# Top_Level.net
KiCad netlist of a schematic drawn in Altium Designer
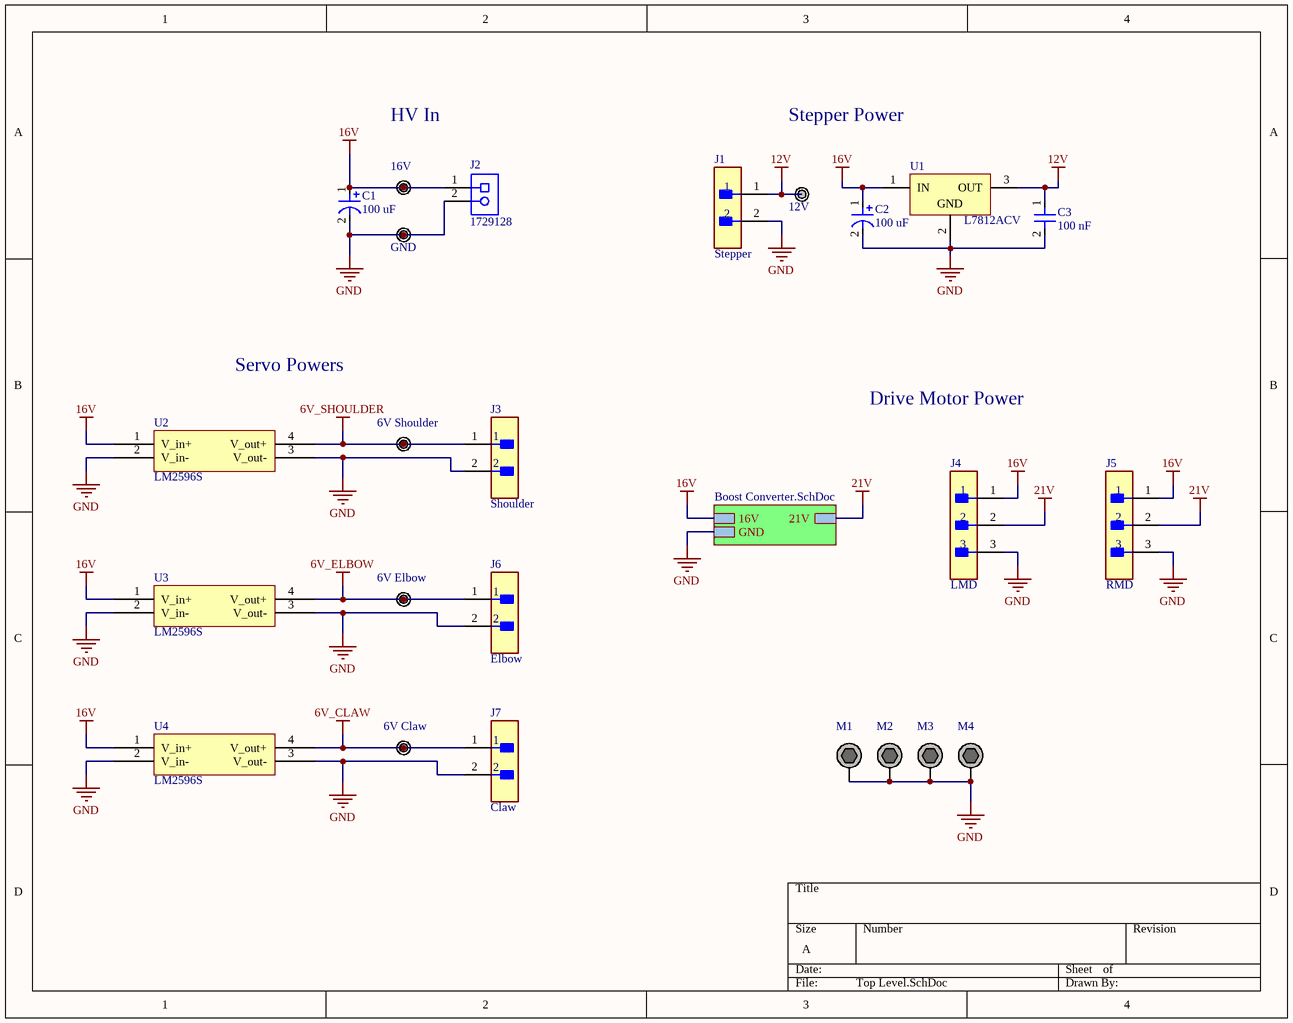
[diagram p0: Top Level.SchDoc]

(export (version "E")
  (design (tool "Eeschema 10.0.6"))
  (components
    (comp (ref "C1")
      (value "100 uF")
      (footprint "PDH_PcbLib:100uF Cap")
      (libsource (lib "PDH_SchLib") (part "100uF cap"))
    )
    (comp (ref "C2")
      (value "100 uF")
      (footprint "PDH_PcbLib:100uF Cap")
      (libsource (lib "PDH_SchLib") (part "100uF cap"))
    )
    (comp (ref "C3")
      (value "100 nF")
      (footprint "PDH_PcbLib:Generic small capacitor")
      (libsource (lib "PDH_SchLib") (part "CAP_GENERIC"))
    )
    (comp (ref "J1")
      (value "Stepper")
      (footprint "FP-B2B-XH-A_LF_SN-MFG")
      (description "CONN HEADER VERT 2POS 2.5MM")
      (libsource (lib "") (part "3bc925449376181038e59eaffc5286c_1"))
    )
    (comp (ref "J2")
      (value "1729128")
      (footprint "PHOE-1729128-2_V")
      (description "PCB Terminal Block, 13.5 A, 400 V, 2-Pin THD, RoHS, Bulk")
      (fields (field (name "MANUFACTURER") "Phoenix Contact"))
      (libsource (lib "Altium Content Vault") (part "CN-2P-F-R2"))
    )
    (comp (ref "J3")
      (value "Shoulder")
      (footprint "FP-B2B-XH-A_LF_SN-MFG")
      (description "CONN HEADER VERT 2POS 2.5MM")
      (libsource (lib "Altium Content Vault") (part "3bc925449376181038e59eaffc5286c"))
    )
    (comp (ref "J4")
      (value "LMD")
      (footprint "FP-B3B-XH-A_LF_SN-MFG")
      (description "CONN HEADER VERT 3POS 2.5MM")
      (libsource (lib "Altium Content Vault") (part "0d3f023dd272f625e17a2be33dea85f"))
    )
    (comp (ref "J5")
      (value "RMD")
      (footprint "FP-B3B-XH-A_LF_SN-MFG")
      (description "CONN HEADER VERT 3POS 2.5MM")
      (libsource (lib "Altium Content Vault") (part "0d3f023dd272f625e17a2be33dea85f"))
    )
    (comp (ref "J6")
      (value "Elbow")
      (footprint "FP-B2B-XH-A_LF_SN-MFG")
      (description "CONN HEADER VERT 2POS 2.5MM")
      (libsource (lib "Altium Content Vault") (part "3bc925449376181038e59eaffc5286c"))
    )
    (comp (ref "J7")
      (value "Claw")
      (footprint "FP-B2B-XH-A_LF_SN-MFG")
      (description "CONN HEADER VERT 2POS 2.5MM")
      (libsource (lib "Altium Content Vault") (part "3bc925449376181038e59eaffc5286c"))
    )
    (comp (ref "M1")
      (value "M3 Mounting Hole Plated")
      (footprint "M3 Screw Hole - Plated")
      (fields (field (name "SOURCE") "UBC Formula Electric.SchLib"))
      (libsource (lib "UBC Formula Electric") (part "Symbol"))
    )
    (comp (ref "M2")
      (value "M3 Mounting Hole Plated")
      (footprint "M3 Screw Hole - Plated")
      (fields (field (name "SOURCE") "UBC Formula Electric.SchLib"))
      (libsource (lib "UBC Formula Electric") (part "Symbol"))
    )
    (comp (ref "M3")
      (value "M3 Mounting Hole Plated")
      (footprint "M3 Screw Hole - Plated")
      (fields (field (name "SOURCE") "UBC Formula Electric.SchLib"))
      (libsource (lib "UBC Formula Electric") (part "Symbol"))
    )
    (comp (ref "M4")
      (value "M3 Mounting Hole Plated")
      (footprint "M3 Screw Hole - Plated")
      (fields (field (name "SOURCE") "UBC Formula Electric.SchLib"))
      (libsource (lib "UBC Formula Electric") (part "Symbol"))
    )
    (comp (ref "TP1")
      (value "16V")
      (footprint "TESTPOINT")
      (fields (field (name "SOURCE") "UBC Formula Electric.SchLib"))
      (libsource (lib "UBC Formula Electric") (part "Thru-Hole Test Point"))
    )
    (comp (ref "TP2")
      (value "12V")
      (footprint "TESTPOINT")
      (fields (field (name "SOURCE") "UBC Formula Electric.SchLib"))
      (libsource (lib "UBC Formula Electric") (part "Thru-Hole Test Point"))
    )
    (comp (ref "TP3")
      (value "GND")
      (footprint "TESTPOINT")
      (fields (field (name "SOURCE") "UBC Formula Electric.SchLib"))
      (libsource (lib "UBC Formula Electric") (part "Thru-Hole Test Point"))
    )
    (comp (ref "TP4")
      (value "6V Shoulder")
      (footprint "TESTPOINT")
      (fields (field (name "SOURCE") "UBC Formula Electric.SchLib"))
      (libsource (lib "UBC Formula Electric") (part "Thru-Hole Test Point"))
    )
    (comp (ref "TP5")
      (value "6V Elbow")
      (footprint "TESTPOINT")
      (fields (field (name "SOURCE") "UBC Formula Electric.SchLib"))
      (libsource (lib "UBC Formula Electric") (part "Thru-Hole Test Point"))
    )
    (comp (ref "TP6")
      (value "6V Claw")
      (footprint "TESTPOINT")
      (fields (field (name "SOURCE") "UBC Formula Electric.SchLib"))
      (libsource (lib "UBC Formula Electric") (part "Thru-Hole Test Point"))
    )
    (comp (ref "U1")
      (value "L7812ACV")
      (footprint "TO220")
      (description "Positive Voltage Regulator, 12V, 3-Pin TO-220")
      (libsource (lib "Altium Content Vault") (part "PM-REG-L4940-SIL3"))
    )
    (comp (ref "U2")
      (value "LM2596S")
      (footprint "PDH_PcbLib:LM2596S")
      (libsource (lib "PDH_SchLib") (part "LM2596S"))
    )
    (comp (ref "U3")
      (value "LM2596S")
      (footprint "PDH_PcbLib:LM2596S")
      (libsource (lib "PDH_SchLib") (part "LM2596S"))
    )
    (comp (ref "U4")
      (value "LM2596S")
      (footprint "PDH_PcbLib:LM2596S")
      (libsource (lib "PDH_SchLib") (part "LM2596S"))
    )
  )
  (nets
    (net (code "1") (name "6V_CLAW") (class "Default")
      (node (ref "J7") (pin "1") (pinfunction "1_1") (pintype "passive"))
      (node (ref "TP6") (pin "1") (pinfunction "TP_1") (pintype "passive"))
      (node (ref "U4") (pin "4") (pinfunction "V_out+_4") (pintype "power_in"))
    )
    (net (code "2") (name "6V_ELBOW") (class "Default")
      (node (ref "J6") (pin "1") (pinfunction "1_1") (pintype "passive"))
      (node (ref "TP5") (pin "1") (pinfunction "TP_1") (pintype "passive"))
      (node (ref "U3") (pin "4") (pinfunction "V_out+_4") (pintype "power_in"))
    )
    (net (code "3") (name "6V_SHOULDER") (class "Default")
      (node (ref "J3") (pin "1") (pinfunction "1_1") (pintype "passive"))
      (node (ref "TP4") (pin "1") (pinfunction "TP_1") (pintype "passive"))
      (node (ref "U2") (pin "4") (pinfunction "V_out+_4") (pintype "power_in"))
    )
    (net (code "4") (name "12V") (class "Default")
      (node (ref "C3") (pin "1") (pintype "passive"))
      (node (ref "J1") (pin "1") (pinfunction "1_1") (pintype "passive"))
      (node (ref "TP2") (pin "1") (pinfunction "TP_1") (pintype "passive"))
      (node (ref "U1") (pin "3") (pinfunction "OUT_3") (pintype "power_in"))
    )
    (net (code "5") (name "16V") (class "Default")
      (node (ref "C1") (pin "1") (pintype "passive"))
      (node (ref "C2") (pin "1") (pintype "passive"))
      (node (ref "J2") (pin "1") (pinfunction "1_1") (pintype "passive"))
      (node (ref "J4") (pin "1") (pinfunction "1_1") (pintype "passive"))
      (node (ref "J5") (pin "1") (pinfunction "1_1") (pintype "passive"))
      (node (ref "TP1") (pin "1") (pinfunction "TP_1") (pintype "passive"))
      (node (ref "U1") (pin "1") (pinfunction "IN_1") (pintype "power_in"))
      (node (ref "U2") (pin "1") (pinfunction "V_in+_1") (pintype "power_in"))
      (node (ref "U3") (pin "1") (pinfunction "V_in+_1") (pintype "power_in"))
      (node (ref "U4") (pin "1") (pinfunction "V_in+_1") (pintype "power_in"))
    )
    (net (code "6") (name "21V") (class "Default")
      (node (ref "J4") (pin "2") (pinfunction "2_2") (pintype "passive"))
      (node (ref "J5") (pin "2") (pinfunction "2_2") (pintype "passive"))
    )
    (net (code "7") (name "GND") (class "Default")
      (node (ref "C1") (pin "2") (pintype "passive"))
      (node (ref "C2") (pin "2") (pintype "passive"))
      (node (ref "C3") (pin "2") (pintype "passive"))
      (node (ref "J1") (pin "2") (pinfunction "2_2") (pintype "passive"))
      (node (ref "J2") (pin "2") (pinfunction "2_2") (pintype "passive"))
      (node (ref "J3") (pin "2") (pinfunction "2_2") (pintype "passive"))
      (node (ref "J4") (pin "3") (pinfunction "3_3") (pintype "passive"))
      (node (ref "J5") (pin "3") (pinfunction "3_3") (pintype "passive"))
      (node (ref "J6") (pin "2") (pinfunction "2_2") (pintype "passive"))
      (node (ref "J7") (pin "2") (pinfunction "2_2") (pintype "passive"))
      (node (ref "M1") (pin "1") (pinfunction "1_1") (pintype "passive"))
      (node (ref "M2") (pin "1") (pinfunction "1_1") (pintype "passive"))
      (node (ref "M3") (pin "1") (pinfunction "1_1") (pintype "passive"))
      (node (ref "M4") (pin "1") (pinfunction "1_1") (pintype "passive"))
      (node (ref "TP3") (pin "1") (pinfunction "TP_1") (pintype "passive"))
      (node (ref "U1") (pin "2") (pinfunction "GND_2") (pintype "power_in"))
      (node (ref "U2") (pin "2") (pinfunction "V_in-_2") (pintype "power_in"))
      (node (ref "U2") (pin "3") (pinfunction "V_out-_3") (pintype "power_in"))
      (node (ref "U3") (pin "2") (pinfunction "V_in-_2") (pintype "power_in"))
      (node (ref "U3") (pin "3") (pinfunction "V_out-_3") (pintype "power_in"))
      (node (ref "U4") (pin "2") (pinfunction "V_in-_2") (pintype "power_in"))
      (node (ref "U4") (pin "3") (pinfunction "V_out-_3") (pintype "power_in"))
    )
  )
)
